# 2-18_11_03_04_02_3.net
KiCad netlist of a schematic drawn in Altium Designer
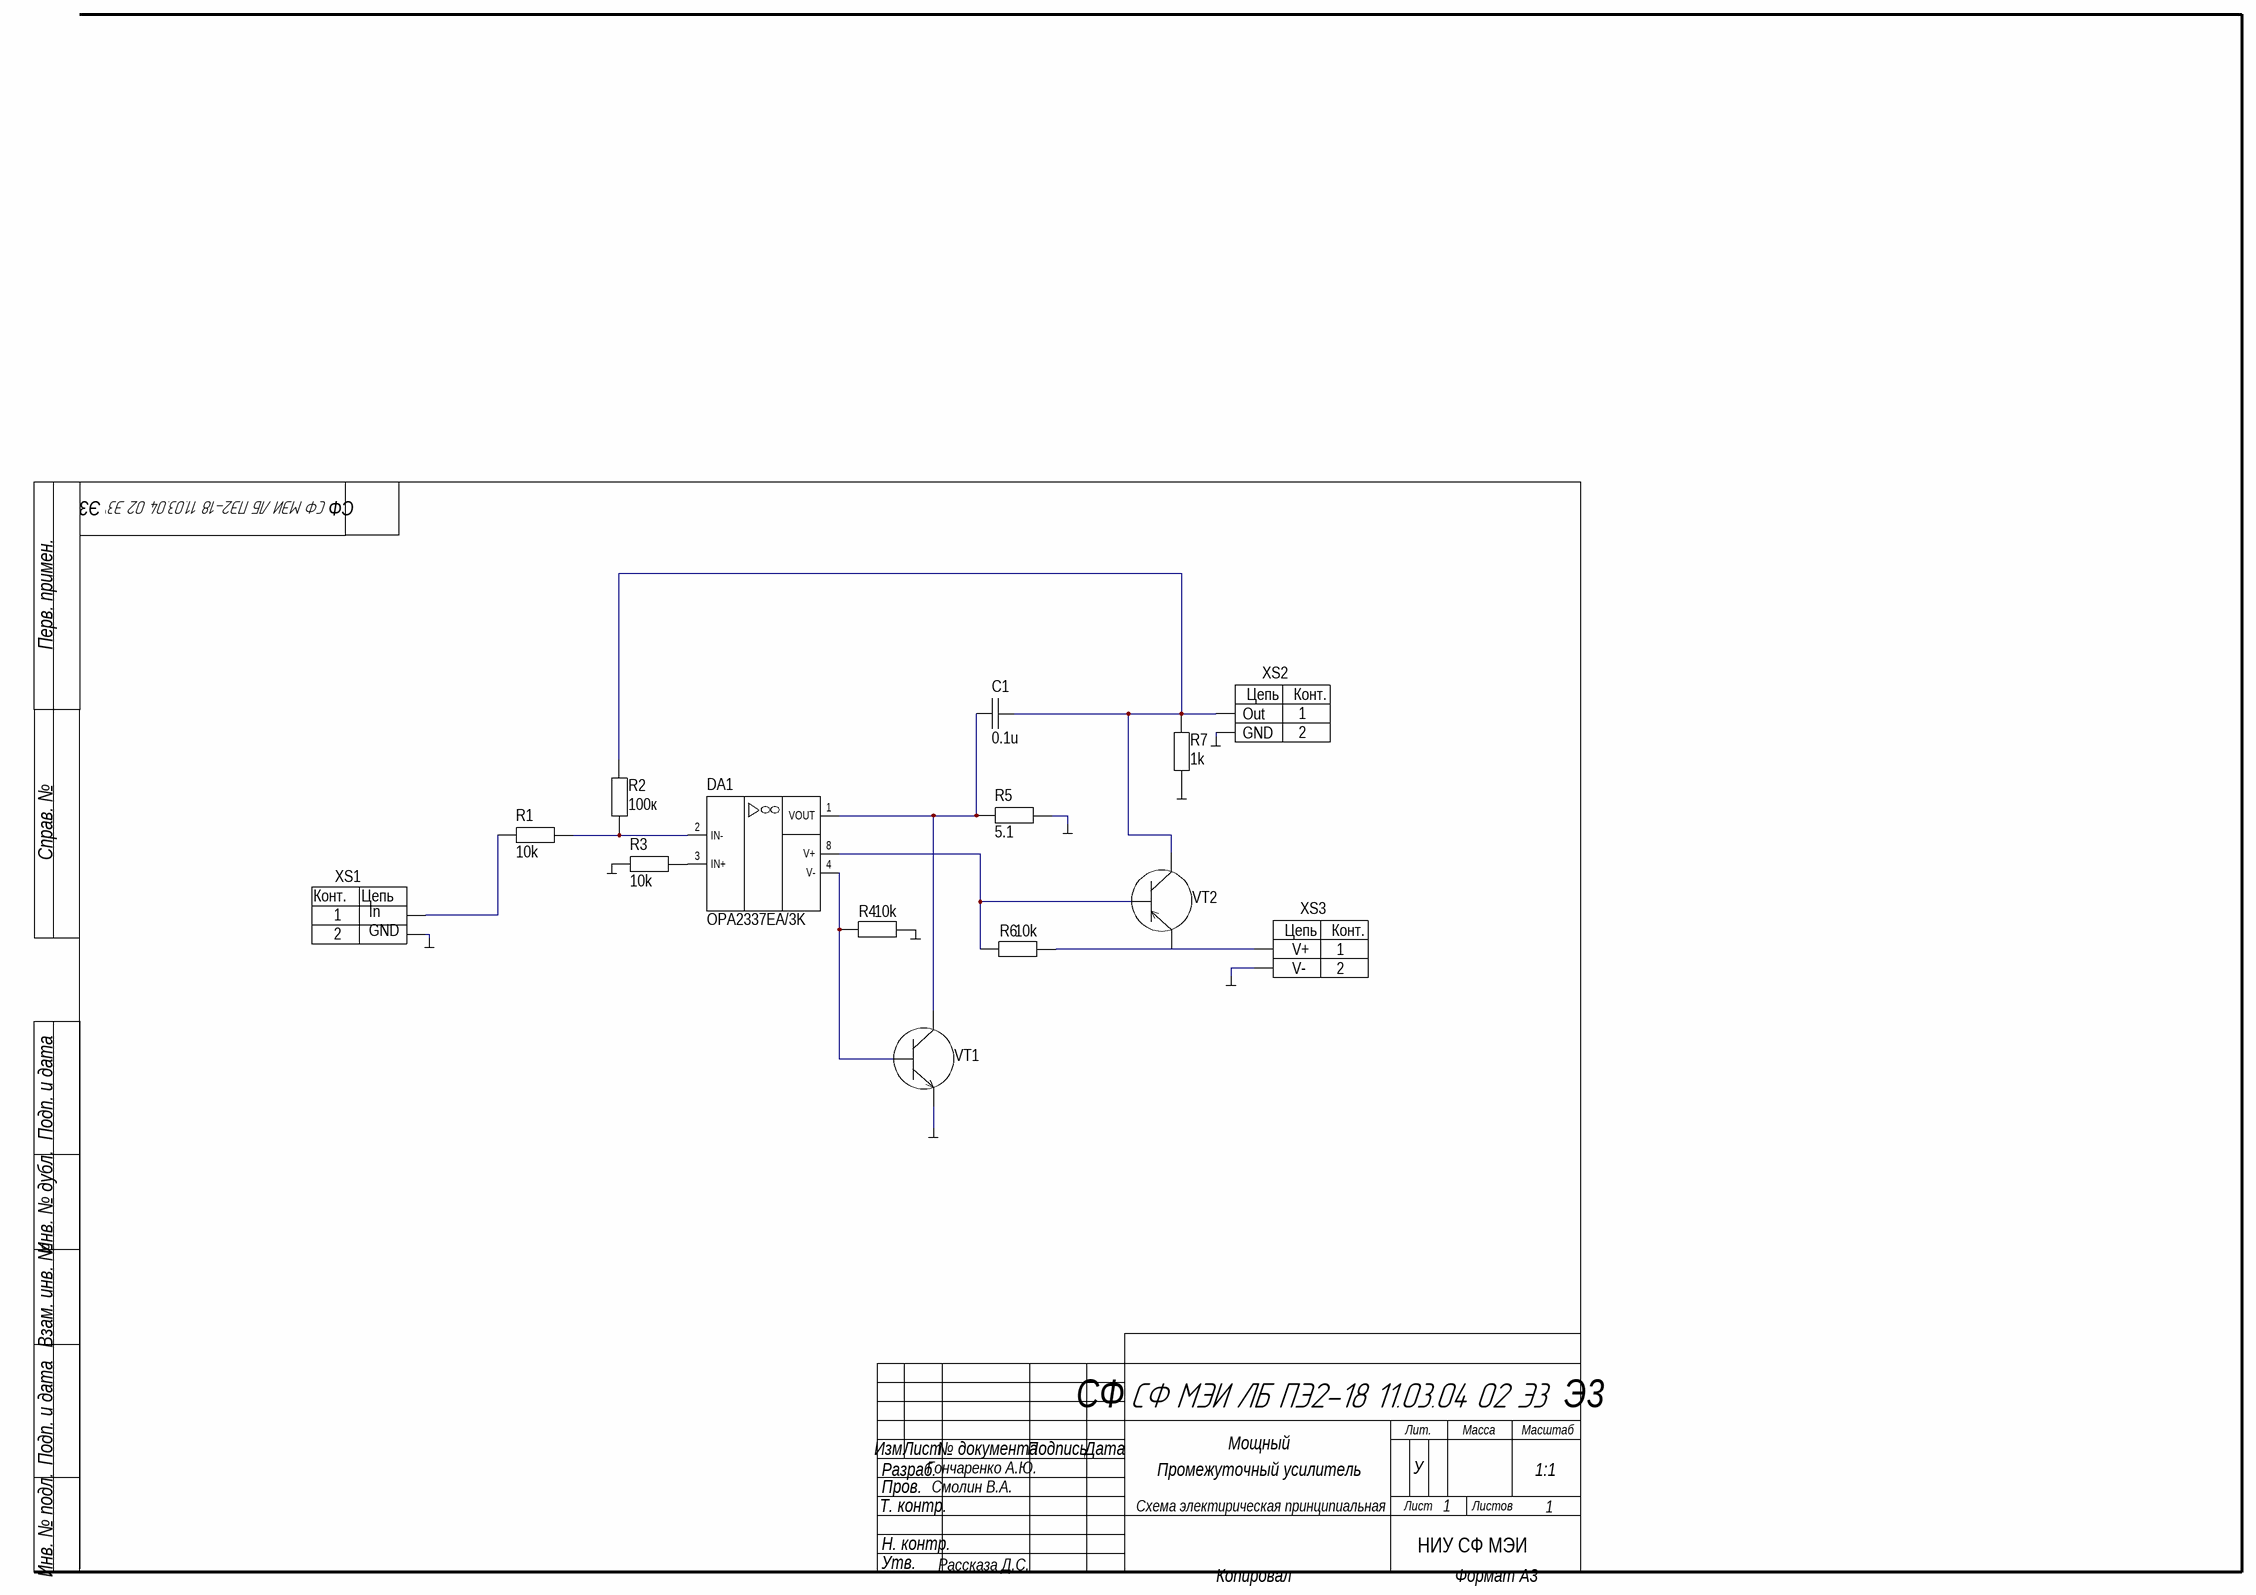
[diagram p0: СФ МЭИ ЛБ ПЭ2-18 11.03.04 02 Э3.SchDoc]

(export (version "E")
  (design (tool "Eeschema 10.0.6"))
  (components
    (comp (ref "C1")
      (value "0.1u")
      (footprint "0805")
      (description "К53-68\"R\"-25В-0.1 мкФ ±10%")
      (libsource (lib "УГО") (part "К53-68{dblquote}R{dblquote}-25В-0.1 мкФ ±10% 0805_1"))
    )
    (comp (ref "DA1")
      (value "OPA2337EA/3K")
      (footprint "SOIC-8")
      (libsource (lib "УГО") (part "OPA2337EA/3K"))
    )
    (comp (ref "R1")
      (value "10k")
      (footprint "0805")
      (description "0805-0.125 Вт -10 кОм±5%")
      (libsource (lib "УГО") (part "0.125Вт 0805 10 кОм, 5%, Чип резистор (SMD)"))
    )
    (comp (ref "R2")
      (value "100к")
      (footprint "0805")
      (description "0805-0.125 Вт -100 кОм±5%")
      (libsource (lib "УГО") (part "0.125Вт 0805 100к кОм, 5%, Чип резистор (SMD)_1"))
    )
    (comp (ref "R3")
      (value "10k")
      (footprint "0805")
      (description "0805-0.125 Вт -10 кОм±5%")
      (libsource (lib "УГО") (part "0.125Вт 0805 10 кОм, 5%, Чип резистор (SMD)"))
    )
    (comp (ref "R4")
      (value "10k")
      (footprint "0805")
      (description "0805-0.125 Вт -10 кОм±5%")
      (libsource (lib "УГО") (part "0.125Вт 0805 10 кОм, 5%, Чип резистор (SMD)"))
    )
    (comp (ref "R5")
      (value "5.1")
      (footprint "0805")
      (description "0805-0.125 Вт -5.1 кОм±5%")
      (libsource (lib "УГО") (part "0.125Вт 0805 5.1 кОм, 5%, Чип резистор (SMD)"))
    )
    (comp (ref "R6")
      (value "10k")
      (footprint "0805")
      (description "0805-0.125 Вт -10 кОм±5%")
      (libsource (lib "УГО") (part "0.125Вт 0805 10 кОм, 5%, Чип резистор (SMD)"))
    )
    (comp (ref "R7")
      (value "1k")
      (footprint "0805")
      (description "0805-0.125 Вт -1 кОм±5%")
      (libsource (lib "УГО") (part "0.125Вт 0805 1 кОм, 5%, Чип резистор (SMD)"))
    )
    (comp (ref "VT1")
      (value "Биполярный транзистор n-p-n")
      (footprint "SOT23")
      (description "2N697")
      (libsource (lib "УГО") (part "2N697"))
    )
    (comp (ref "VT2")
      (value "Биполярный транзистор p-n-p")
      (footprint "SOT23")
      (description "2N2338")
      (libsource (lib "УГО") (part "2N2338"))
    )
    (comp (ref "XS1") (value "SM02B") (footprint "CI1102M1H  (F)") (libsource (lib "УГО") (part "SM02B")))
    (comp (ref "XS2") (value "SM02B") (footprint "CI1102M1H  (F)") (libsource (lib "УГО") (part "SM02B")))
    (comp (ref "XS3") (value "SM02B") (footprint "CI1102M1H  (F)") (libsource (lib "УГО") (part "SM02B")))
  )
  (nets
    (net (code "1") (name "<NO NET>") (class "Default")
      (node (ref "R3") (pin "1") (pinfunction "1_1") (pintype "passive"))
      (node (ref "R4") (pin "2") (pinfunction "2_2") (pintype "passive"))
      (node (ref "R5") (pin "2") (pinfunction "2_2") (pintype "passive"))
      (node (ref "R7") (pin "1") (pinfunction "1_1") (pintype "passive"))
      (node (ref "VT1") (pin "3") (pinfunction "K_3") (pintype "passive"))
      (node (ref "XS1") (pin "2") (pinfunction "Pin2_2") (pintype "passive"))
      (node (ref "XS2") (pin "2") (pinfunction "Pin2_2") (pintype "passive"))
      (node (ref "XS3") (pin "2") (pinfunction "Pin2_2") (pintype "passive"))
    )
    (net (code "2") (name "Net-(DA1-IN+)") (class "Default")
      (node (ref "DA1") (pin "3") (pinfunction "IN+_3") (pintype "passive"))
      (node (ref "R3") (pin "2") (pinfunction "2_2") (pintype "passive"))
    )
    (net (code "3") (name "Net-(DA1-IN-)") (class "Default")
      (node (ref "DA1") (pin "2") (pinfunction "IN-_2") (pintype "passive"))
      (node (ref "R1") (pin "2") (pinfunction "2_2") (pintype "passive"))
      (node (ref "R2") (pin "1") (pinfunction "1_1") (pintype "passive"))
    )
    (net (code "4") (name "Net-(DA1-V+)") (class "Default")
      (node (ref "DA1") (pin "8") (pinfunction "V+_8") (pintype "passive"))
      (node (ref "R6") (pin "1") (pinfunction "1_1") (pintype "passive"))
      (node (ref "VT2") (pin "1") (pinfunction "B_1") (pintype "passive"))
    )
    (net (code "5") (name "Net-(DA1-V-)") (class "Default")
      (node (ref "DA1") (pin "4") (pinfunction "V-_4") (pintype "passive"))
      (node (ref "R4") (pin "1") (pinfunction "1_1") (pintype "passive"))
      (node (ref "VT1") (pin "1") (pinfunction "B_1") (pintype "passive"))
    )
    (net (code "6") (name "Net-(DA1-VOUT)") (class "Default")
      (node (ref "C1") (pin "1") (pinfunction "1_1") (pintype "passive"))
      (node (ref "DA1") (pin "1") (pinfunction "VOUT_1") (pintype "passive"))
      (node (ref "R5") (pin "1") (pinfunction "1_1") (pintype "passive"))
      (node (ref "VT1") (pin "2") (pinfunction "E_2") (pintype "passive"))
    )
    (net (code "7") (name "Net-(VT2-E)") (class "Default")
      (node (ref "C1") (pin "2") (pinfunction "2_2") (pintype "passive"))
      (node (ref "R2") (pin "2") (pinfunction "2_2") (pintype "passive"))
      (node (ref "R7") (pin "2") (pinfunction "2_2") (pintype "passive"))
      (node (ref "VT2") (pin "2") (pinfunction "E_2") (pintype "passive"))
      (node (ref "XS2") (pin "1") (pinfunction "Pin1_1") (pintype "passive"))
    )
    (net (code "8") (name "Net-(XS1-Pin1)") (class "Default")
      (node (ref "R1") (pin "1") (pinfunction "1_1") (pintype "passive"))
      (node (ref "XS1") (pin "1") (pinfunction "Pin1_1") (pintype "passive"))
    )
    (net (code "9") (name "Net-(XS3-Pin1)") (class "Default")
      (node (ref "R6") (pin "2") (pinfunction "2_2") (pintype "passive"))
      (node (ref "XS3") (pin "1") (pinfunction "Pin1_1") (pintype "passive"))
    )
    (net (code "10") (name "unconnected-(VT2-K-Pad3)") (class "Default")
      (node (ref "VT2") (pin "3") (pinfunction "K_3") (pintype "passive"))
    )
  )
)
